# TPS63020.net
KiCad netlist of a schematic drawn in Altium Designer
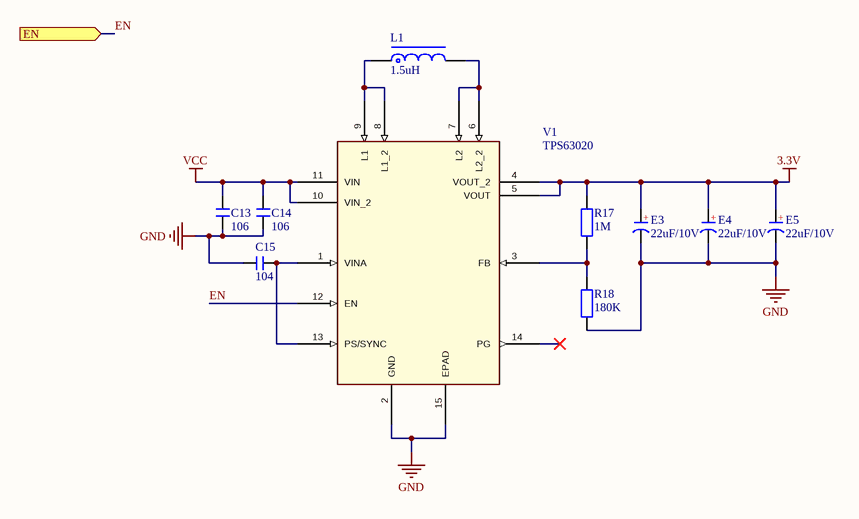
[diagram p0: TPS63020电源模块.SchDoc]

(export (version "E")
  (design (tool "Eeschema 10.0.6"))
  (components
    (comp (ref "C13")
      (value "106")
      (footprint "C 0603_L")
      (description "无极性贴片电容")
      (fields (field (name "版权归属") "黎明电子style"))
      (libsource (lib "3.3   - 电容capacitor") (part "C"))
    )
    (comp (ref "C14")
      (value "106")
      (footprint "C 0603_L")
      (description "无极性贴片电容")
      (fields (field (name "版权归属") "黎明电子style"))
      (libsource (lib "3.3   - 电容capacitor") (part "C"))
    )
    (comp (ref "C15")
      (value "104")
      (footprint "C 0603_L")
      (description "无极性贴片电容")
      (fields (field (name "版权归属") "黎明电子style"))
      (libsource (lib "3.3   - 电容capacitor") (part "C"))
    )
    (comp (ref "E3")
      (value "22uF/10V")
      (footprint "CD A(3216)")
      (description "贴片钽电容")
      (fields (field (name "版权归属") "黎明电子style"))
      (libsource (lib "3.3   - 电容capacitor") (part "C-CD"))
    )
    (comp (ref "E4")
      (value "22uF/10V")
      (footprint "CD A(3216)")
      (description "贴片钽电容")
      (fields (field (name "版权归属") "黎明电子style"))
      (libsource (lib "3.3   - 电容capacitor") (part "C-CD"))
    )
    (comp (ref "E5")
      (value "22uF/10V")
      (footprint "CD A(3216)")
      (description "贴片钽电容")
      (fields (field (name "版权归属") "黎明电子style"))
      (libsource (lib "3.3   - 电容capacitor") (part "C-CD"))
    )
    (comp (ref "L1")
      (value "1.5uH")
      (footprint "SMD,4.75x4.45x2mm")
      (description "贴片功率电感")
      (fields (field (name "版权归属") "黎明电子style"))
      (libsource (lib "3.2   - 电感Inductor") (part "L-CD"))
    )
    (comp (ref "R17")
      (value "1M")
      (footprint "R 0603_L")
      (description "贴片电阻")
      (fields (field (name "版权归属") "黎明电子style"))
      (libsource (lib "3.4   - 电阻Resistor") (part "R"))
    )
    (comp (ref "R18")
      (value "180K")
      (footprint "R 0603_L")
      (description "贴片电阻")
      (fields (field (name "版权归属") "黎明电子style"))
      (libsource (lib "3.4   - 电阻Resistor") (part "R"))
    )
    (comp (ref "V1")
      (value "TPS63020")
      (footprint "VSON - 14")
      (description "单电感器降压/升压转换器   High Efficiency Single Inductor Buck-Boost Converter with 4A Switch")
      (libsource (lib "1.3   - 电源类芯片") (part "TPS63020"))
    )
  )
  (nets
    (net (code "1") (name "/EN") (class "Default")
      (node (ref "V1") (pin "12") (pinfunction "EN_12") (pintype "input"))
    )
    (net (code "2") (name "3.3V") (class "Default")
      (node (ref "E3") (pin "1") (pinfunction "A_1") (pintype "passive"))
      (node (ref "E4") (pin "1") (pinfunction "A_1") (pintype "passive"))
      (node (ref "E5") (pin "1") (pinfunction "A_1") (pintype "passive"))
      (node (ref "R17") (pin "2") (pinfunction "2_2") (pintype "passive"))
      (node (ref "V1") (pin "4") (pinfunction "VOUT_2_4") (pintype "power_in"))
      (node (ref "V1") (pin "5") (pinfunction "VOUT_5") (pintype "power_in"))
    )
    (net (code "3") (name "GND") (class "Default")
      (node (ref "C13") (pin "2") (pinfunction "2_2") (pintype "passive"))
      (node (ref "C14") (pin "2") (pinfunction "2_2") (pintype "passive"))
      (node (ref "C15") (pin "1") (pinfunction "1_1") (pintype "passive"))
      (node (ref "E3") (pin "2") (pinfunction "K_2") (pintype "passive"))
      (node (ref "E4") (pin "2") (pinfunction "K_2") (pintype "passive"))
      (node (ref "E5") (pin "2") (pinfunction "K_2") (pintype "passive"))
      (node (ref "R18") (pin "1") (pinfunction "1_1") (pintype "passive"))
      (node (ref "V1") (pin "15") (pinfunction "EPAD_15") (pintype "passive"))
      (node (ref "V1") (pin "2") (pinfunction "GND_2") (pintype "power_in"))
    )
    (net (code "4") (name "Net-(V1-FB)") (class "Default")
      (node (ref "R17") (pin "1") (pinfunction "1_1") (pintype "passive"))
      (node (ref "R18") (pin "2") (pinfunction "2_2") (pintype "passive"))
      (node (ref "V1") (pin "3") (pinfunction "FB_3") (pintype "input"))
    )
    (net (code "5") (name "Net-(V1-L1)") (class "Default")
      (node (ref "L1") (pin "1") (pinfunction "1_1") (pintype "passive"))
      (node (ref "V1") (pin "8") (pinfunction "L1_2_8") (pintype "input"))
      (node (ref "V1") (pin "9") (pinfunction "L1_9") (pintype "input"))
    )
    (net (code "6") (name "Net-(V1-L2)") (class "Default")
      (node (ref "L1") (pin "2") (pinfunction "2_2") (pintype "passive"))
      (node (ref "V1") (pin "6") (pinfunction "L2_2_6") (pintype "input"))
      (node (ref "V1") (pin "7") (pinfunction "L2_7") (pintype "input"))
    )
    (net (code "7") (name "Net-(V1-PS{slash}SYNC)") (class "Default")
      (node (ref "C15") (pin "2") (pinfunction "2_2") (pintype "passive"))
      (node (ref "V1") (pin "1") (pinfunction "VINA_1") (pintype "input"))
      (node (ref "V1") (pin "13") (pinfunction "PS/SYNC_13") (pintype "input"))
    )
    (net (code "8") (name "VCC") (class "Default")
      (node (ref "C13") (pin "1") (pinfunction "1_1") (pintype "passive"))
      (node (ref "C14") (pin "1") (pinfunction "1_1") (pintype "passive"))
      (node (ref "V1") (pin "10") (pinfunction "VIN_2_10") (pintype "power_in"))
      (node (ref "V1") (pin "11") (pinfunction "VIN_11") (pintype "power_in"))
    )
    (net (code "9") (name "unconnected-(V1-PG-Pad14)") (class "Default")
      (node (ref "V1") (pin "14") (pinfunction "PG_14") (pintype "output+no_connect"))
    )
  )
)
